# CPU_POWER.net
KiCad netlist of a schematic drawn in Altium Designer
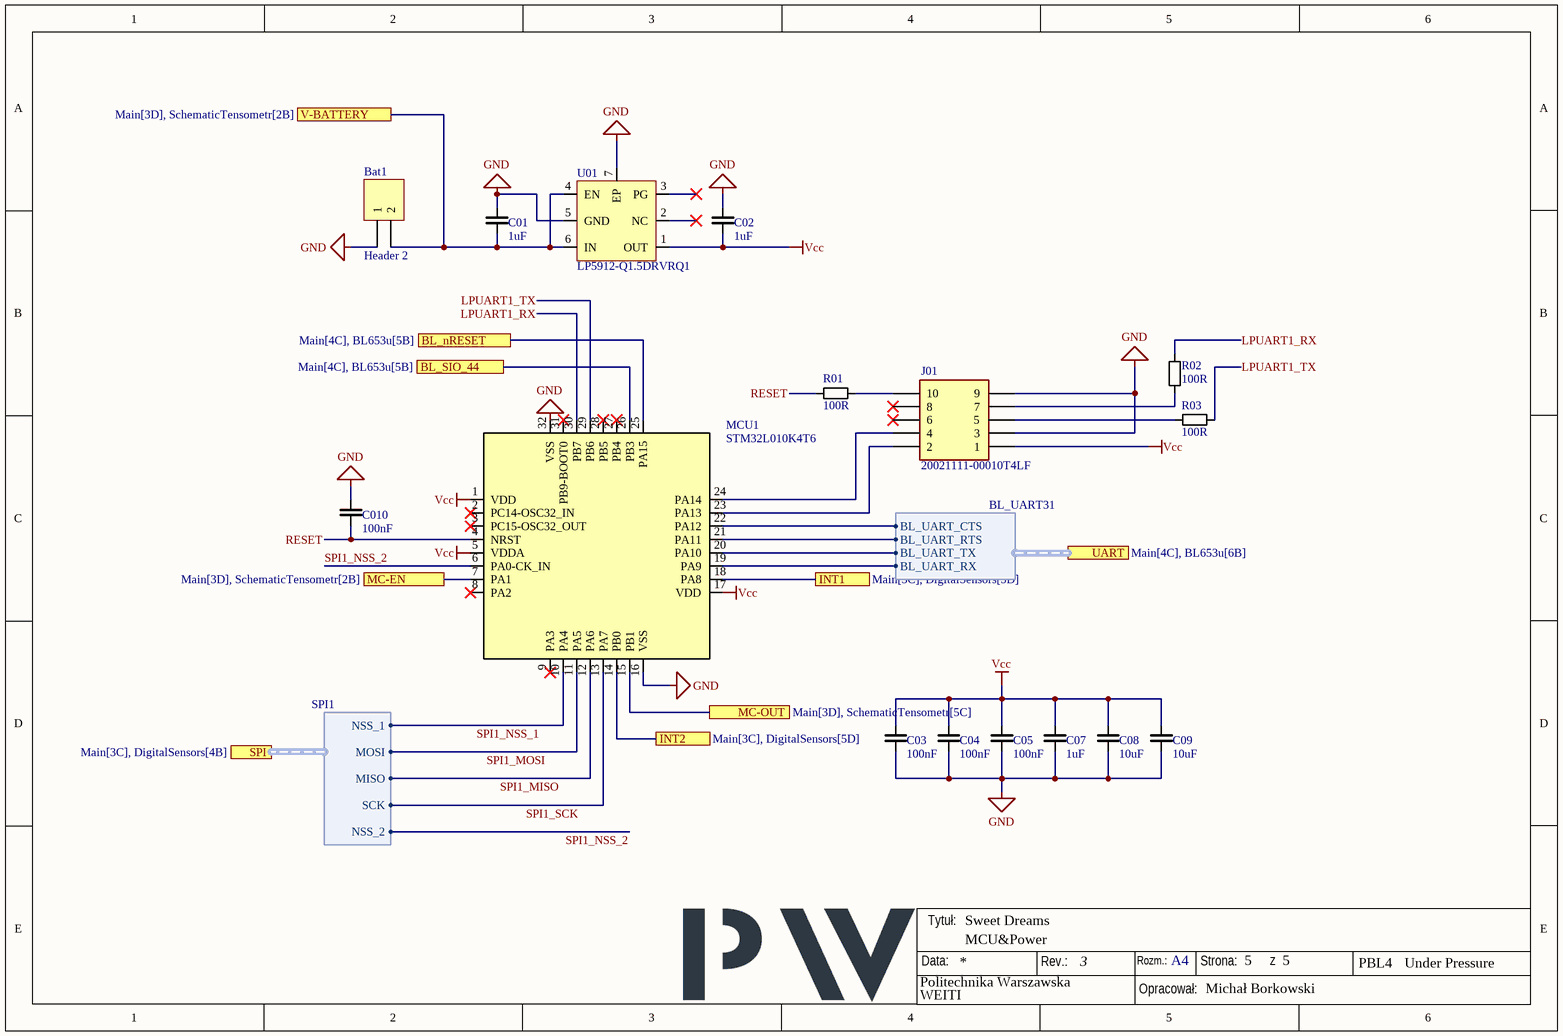
[diagram p0: CPU&POWER.SchDoc]

(export (version "E")
  (design (tool "Eeschema 10.0.6"))
  (components
    (comp (ref "Bat1")
      (value "Header 2")
      (footprint "HDR1X2")
      (description "Header, 2-Pin")
      (fields (field (name "PUBLISHER") "Altium Limited"))
      (libsource (lib "Miscellaneous Connectors") (part "Header 2"))
    )
    (comp (ref "C01")
      (value "1uF")
      (footprint "0402_CAP")
      (description "Ceramic capacitor")
      (libsource (lib "Cap") (part "Cap"))
    )
    (comp (ref "C02")
      (value "1uF")
      (footprint "0402_CAP")
      (description "Ceramic capacitor")
      (libsource (lib "Cap") (part "Cap"))
    )
    (comp (ref "C03")
      (value "100nF")
      (footprint "0402_CAP")
      (description "Ceramic capacitor")
      (libsource (lib "Cap") (part "Cap"))
    )
    (comp (ref "C04")
      (value "100nF")
      (footprint "0402_CAP")
      (description "Ceramic capacitor")
      (libsource (lib "Cap") (part "Cap"))
    )
    (comp (ref "C05")
      (value "100nF")
      (footprint "0402_CAP")
      (description "Ceramic capacitor")
      (libsource (lib "Cap") (part "Cap"))
    )
    (comp (ref "C07")
      (value "1uF")
      (footprint "0402_CAP")
      (description "Ceramic capacitor")
      (libsource (lib "Cap") (part "Cap"))
    )
    (comp (ref "C08")
      (value "10uF")
      (footprint "0402_CAP")
      (description "Ceramic capacitor")
      (libsource (lib "Cap") (part "Cap"))
    )
    (comp (ref "C09")
      (value "10uF")
      (footprint "0402_CAP")
      (description "Ceramic capacitor")
      (libsource (lib "Cap") (part "Cap"))
    )
    (comp (ref "C010")
      (value "100nF")
      (footprint "0402_CAP")
      (description "Ceramic capacitor")
      (libsource (lib "Cap") (part "Cap"))
    )
    (comp (ref "J01")
      (value "20021111-00010T4LF")
      (footprint "HDRV10W41P127_2X5_635X343X575P_m")
      (description "Connector")
      (fields (field (name "MOUSER PART NUMBER") "649-221111-00010T4LF"))
      (libsource (lib "SamacSys") (part "20021111-00010T4LF"))
    )
    (comp (ref "MCU1")
      (value "STM32L010K4T6")
      (footprint "QFP80P900X900X160-32N_m")
      (libsource (lib "parts1") (part "CPU32p"))
    )
    (comp (ref "R01")
      (value "100R")
      (footprint "0402_RES")
      (description "Resistor")
      (libsource (lib "RES") (part "RES"))
    )
    (comp (ref "R02")
      (value "100R")
      (footprint "0402_RES")
      (description "Resistor")
      (libsource (lib "RES") (part "RES"))
    )
    (comp (ref "R03")
      (value "100R")
      (footprint "0402_RES")
      (description "Resistor")
      (libsource (lib "RES") (part "RES"))
    )
    (comp (ref "U01")
      (value "LP5912-Q1.5DRVRQ1")
      (footprint "SON65P200X200X80-7N_m")
      (libsource (lib "parts1") (part "STAB"))
    )
  )
  (nets
    (net (code "3") (name "/BL_SIO_44") (class "Default")
      (node (ref "MCU1") (pin "26") (pinfunction "PB3_26") (pintype "passive"))
    )
    (net (code "4") (name "/BL_UART_CTS") (class "Default")
      (node (ref "MCU1") (pin "22") (pinfunction "PA12_22") (pintype "passive"))
    )
    (net (code "5") (name "/BL_UART_RTS") (class "Default")
      (node (ref "MCU1") (pin "21") (pinfunction "PA11_21") (pintype "passive"))
    )
    (net (code "6") (name "/BL_UART_RX") (class "Default")
      (node (ref "MCU1") (pin "19") (pinfunction "PA9_19") (pintype "passive"))
    )
    (net (code "7") (name "/BL_UART_TX") (class "Default")
      (node (ref "MCU1") (pin "20") (pinfunction "PA10_20") (pintype "passive"))
    )
    (net (code "8") (name "/BL_nRESET") (class "Default")
      (node (ref "MCU1") (pin "25") (pinfunction "PA15_25") (pintype "passive"))
    )
    (net (code "9") (name "/INT1") (class "Default")
      (node (ref "MCU1") (pin "18") (pinfunction "PA8_18") (pintype "passive"))
    )
    (net (code "10") (name "/INT2") (class "Default")
      (node (ref "MCU1") (pin "14") (pinfunction "PB0_14") (pintype "passive"))
    )
    (net (code "11") (name "/LPUART1_RX") (class "Default")
      (node (ref "MCU1") (pin "30") (pinfunction "PB7_30") (pintype "passive"))
      (node (ref "R02") (pin "2") (pinfunction "2_2") (pintype "passive"))
    )
    (net (code "12") (name "/LPUART1_TX") (class "Default")
      (node (ref "MCU1") (pin "29") (pinfunction "PB6_29") (pintype "passive"))
      (node (ref "R03") (pin "1") (pinfunction "1_1") (pintype "passive"))
    )
    (net (code "13") (name "/MC-EN") (class "Default")
      (node (ref "MCU1") (pin "7") (pinfunction "PA1_7") (pintype "passive"))
    )
    (net (code "14") (name "/MC-OUT") (class "Default")
      (node (ref "MCU1") (pin "15") (pinfunction "PB1_15") (pintype "passive"))
    )
    (net (code "15") (name "/RESET") (class "Default")
      (node (ref "C010") (pin "1") (pinfunction "1_1") (pintype "passive"))
      (node (ref "MCU1") (pin "4") (pinfunction "NRST_4") (pintype "passive"))
      (node (ref "R01") (pin "1") (pinfunction "1_1") (pintype "passive"))
    )
    (net (code "16") (name "/SPI1_MISO") (class "Default")
      (node (ref "MCU1") (pin "12") (pinfunction "PA6_12") (pintype "passive"))
    )
    (net (code "17") (name "/SPI1_MOSI") (class "Default")
      (node (ref "MCU1") (pin "11") (pinfunction "PA5_11") (pintype "passive"))
    )
    (net (code "18") (name "/SPI1_NSS_1") (class "Default")
      (node (ref "MCU1") (pin "10") (pinfunction "PA4_10") (pintype "passive"))
    )
    (net (code "19") (name "/SPI1_NSS_2") (class "Default")
      (node (ref "MCU1") (pin "6") (pinfunction "PA0-CK_IN_6") (pintype "passive"))
    )
    (net (code "20") (name "/SPI1_SCK") (class "Default")
      (node (ref "MCU1") (pin "13") (pinfunction "PA7_13") (pintype "passive"))
    )
    (net (code "21") (name "/V-BATTERY") (class "Default")
      (node (ref "Bat1") (pin "2") (pinfunction "2_2") (pintype "passive"))
      (node (ref "C01") (pin "1") (pinfunction "1_1") (pintype "passive"))
      (node (ref "U01") (pin "4") (pinfunction "EN_4") (pintype "passive"))
      (node (ref "U01") (pin "6") (pinfunction "IN_6") (pintype "passive"))
    )
    (net (code "24") (name "GND") (class "Default")
      (node (ref "Bat1") (pin "1") (pinfunction "1_1") (pintype "passive"))
      (node (ref "C01") (pin "2") (pinfunction "2_2") (pintype "passive"))
      (node (ref "C010") (pin "2") (pinfunction "2_2") (pintype "passive"))
      (node (ref "C02") (pin "2") (pinfunction "2_2") (pintype "passive"))
      (node (ref "C03") (pin "1") (pinfunction "1_1") (pintype "passive"))
      (node (ref "C04") (pin "1") (pinfunction "1_1") (pintype "passive"))
      (node (ref "C05") (pin "1") (pinfunction "1_1") (pintype "passive"))
      (node (ref "C07") (pin "1") (pinfunction "1_1") (pintype "passive"))
      (node (ref "C08") (pin "1") (pinfunction "1_1") (pintype "passive"))
      (node (ref "C09") (pin "1") (pinfunction "1_1") (pintype "passive"))
      (node (ref "J01") (pin "3") (pinfunction "3_3") (pintype "passive"))
      (node (ref "J01") (pin "9") (pinfunction "9_9") (pintype "passive"))
      (node (ref "MCU1") (pin "16") (pinfunction "VSS_16") (pintype "passive"))
      (node (ref "MCU1") (pin "32") (pinfunction "VSS_32") (pintype "passive"))
      (node (ref "U01") (pin "5") (pinfunction "GND_5") (pintype "passive"))
      (node (ref "U01") (pin "7") (pinfunction "EP_7") (pintype "passive"))
    )
    (net (code "25") (name "Net-(J01-Pad5)") (class "Default")
      (node (ref "J01") (pin "5") (pinfunction "5_5") (pintype "passive"))
      (node (ref "R03") (pin "2") (pinfunction "2_2") (pintype "passive"))
    )
    (net (code "26") (name "Net-(J01-Pad7)") (class "Default")
      (node (ref "J01") (pin "7") (pinfunction "7_7") (pintype "passive"))
      (node (ref "R02") (pin "1") (pinfunction "1_1") (pintype "passive"))
    )
    (net (code "27") (name "Net-(J01-Pad10)") (class "Default")
      (node (ref "J01") (pin "10") (pinfunction "10_10") (pintype "passive"))
      (node (ref "R01") (pin "2") (pinfunction "2_2") (pintype "passive"))
    )
    (net (code "28") (name "Net-(MCU1-PA13)") (class "Default")
      (node (ref "J01") (pin "2") (pinfunction "2_2") (pintype "passive"))
      (node (ref "MCU1") (pin "23") (pinfunction "PA13_23") (pintype "passive"))
    )
    (net (code "29") (name "Net-(MCU1-PA14)") (class "Default")
      (node (ref "J01") (pin "4") (pinfunction "4_4") (pintype "passive"))
      (node (ref "MCU1") (pin "24") (pinfunction "PA14_24") (pintype "passive"))
    )
    (net (code "30") (name "Vcc") (class "Default")
      (node (ref "C02") (pin "1") (pinfunction "1_1") (pintype "passive"))
      (node (ref "C03") (pin "2") (pinfunction "2_2") (pintype "passive"))
      (node (ref "C04") (pin "2") (pinfunction "2_2") (pintype "passive"))
      (node (ref "C05") (pin "2") (pinfunction "2_2") (pintype "passive"))
      (node (ref "C07") (pin "2") (pinfunction "2_2") (pintype "passive"))
      (node (ref "C08") (pin "2") (pinfunction "2_2") (pintype "passive"))
      (node (ref "C09") (pin "2") (pinfunction "2_2") (pintype "passive"))
      (node (ref "J01") (pin "1") (pinfunction "1_1") (pintype "passive"))
      (node (ref "MCU1") (pin "1") (pinfunction "VDD_1") (pintype "passive"))
      (node (ref "MCU1") (pin "17") (pinfunction "VDD_17") (pintype "passive"))
      (node (ref "MCU1") (pin "5") (pinfunction "VDDA_5") (pintype "passive"))
      (node (ref "U01") (pin "1") (pinfunction "OUT_1") (pintype "passive"))
    )
    (net (code "31") (name "unconnected-(J01-Pad6)") (class "Default")
      (node (ref "J01") (pin "6") (pinfunction "6_6") (pintype "passive+no_connect"))
    )
    (net (code "32") (name "unconnected-(J01-Pad8)") (class "Default")
      (node (ref "J01") (pin "8") (pinfunction "8_8") (pintype "passive+no_connect"))
    )
    (net (code "33") (name "unconnected-(MCU1-PA2-Pad8)") (class "Default")
      (node (ref "MCU1") (pin "8") (pinfunction "PA2_8") (pintype "passive+no_connect"))
    )
    (net (code "34") (name "unconnected-(MCU1-PA3-Pad9)") (class "Default")
      (node (ref "MCU1") (pin "9") (pinfunction "PA3_9") (pintype "passive+no_connect"))
    )
    (net (code "35") (name "unconnected-(MCU1-PB4-Pad27)") (class "Default")
      (node (ref "MCU1") (pin "27") (pinfunction "PB4_27") (pintype "passive+no_connect"))
    )
    (net (code "36") (name "unconnected-(MCU1-PB5-Pad28)") (class "Default")
      (node (ref "MCU1") (pin "28") (pinfunction "PB5_28") (pintype "passive+no_connect"))
    )
    (net (code "37") (name "unconnected-(MCU1-PB9-BOOT0-Pad31)") (class "Default")
      (node (ref "MCU1") (pin "31") (pinfunction "PB9-BOOT0_31") (pintype "passive+no_connect"))
    )
    (net (code "38") (name "unconnected-(MCU1-PC14-OSC32_IN-Pad2)") (class "Default")
      (node (ref "MCU1") (pin "2") (pinfunction "PC14-OSC32_IN_2") (pintype "passive+no_connect"))
    )
    (net (code "39") (name "unconnected-(MCU1-PC15-OSC32_OUT-Pad3)") (class "Default")
      (node (ref "MCU1") (pin "3") (pinfunction "PC15-OSC32_OUT_3") (pintype "passive+no_connect"))
    )
    (net (code "40") (name "unconnected-(U01-NC-Pad2)") (class "Default")
      (node (ref "U01") (pin "2") (pinfunction "NC_2") (pintype "passive+no_connect"))
    )
    (net (code "41") (name "unconnected-(U01-PG-Pad3)") (class "Default")
      (node (ref "U01") (pin "3") (pinfunction "PG_3") (pintype "passive+no_connect"))
    )
  )
)
